# fm_1.net
KiCad netlist of a schematic drawn in EAGLE
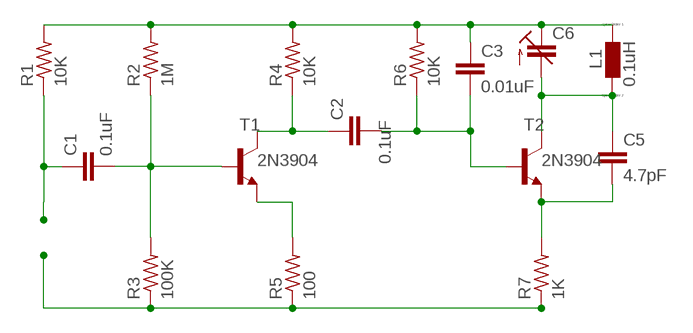
[diagram p0: schematic, sheet 1]

(export (version "E")
  (design (tool "Eeschema 10.0.6"))
  (components
    (comp (ref "C1")
      (value "0.1uF")
      (footprint "eagle-import:C025-040X050")
      (libsource (lib "eagle-import") (part "C-EU025-040X050"))
    )
    (comp (ref "C2")
      (value "0.1uF")
      (footprint "eagle-import:C025-040X050")
      (libsource (lib "eagle-import") (part "C-EU025-040X050"))
    )
    (comp (ref "C3")
      (value "0.01uF")
      (footprint "eagle-import:C025-040X050")
      (libsource (lib "eagle-import") (part "C-EU025-040X050"))
    )
    (comp (ref "C5")
      (value "4.7pF")
      (footprint "eagle-import:C025-040X050")
      (libsource (lib "eagle-import") (part "C-EU025-040X050"))
    )
    (comp (ref "C6")
      (value "C-TRIMM808")
      (footprint "eagle-import:CTRIM808-BC")
      (libsource (lib "eagle-import") (part "C-TRIMM808"))
    )
    (comp (ref "L1")
      (value "0.1uH")
      (footprint "eagle-import:0204_7")
      (libsource (lib "eagle-import") (part "L0204/7"))
    )
    (comp (ref "R1")
      (value "10K")
      (footprint "eagle-import:0204V")
      (libsource (lib "eagle-import") (part "R-US_0204/2V"))
    )
    (comp (ref "R2")
      (value "1M")
      (footprint "eagle-import:0204V")
      (libsource (lib "eagle-import") (part "R-US_0204/2V"))
    )
    (comp (ref "R3")
      (value "100K")
      (footprint "eagle-import:0204V")
      (libsource (lib "eagle-import") (part "R-US_0204/2V"))
    )
    (comp (ref "R4")
      (value "10K")
      (footprint "eagle-import:0204V")
      (libsource (lib "eagle-import") (part "R-US_0204/2V"))
    )
    (comp (ref "R5")
      (value "100")
      (footprint "eagle-import:0204V")
      (libsource (lib "eagle-import") (part "R-US_0204/2V"))
    )
    (comp (ref "R6")
      (value "10K")
      (footprint "eagle-import:0204V")
      (libsource (lib "eagle-import") (part "R-US_0204/2V"))
    )
    (comp (ref "R7")
      (value "1K")
      (footprint "eagle-import:0204V")
      (libsource (lib "eagle-import") (part "R-US_0204/2V"))
    )
    (comp (ref "T1")
      (value "2N3904")
      (footprint "eagle-import:TO92")
      (libsource (lib "eagle-import") (part "2N3904"))
    )
    (comp (ref "T2")
      (value "2N3904")
      (footprint "eagle-import:TO92")
      (libsource (lib "eagle-import") (part "2N3904"))
    )
  )
  (nets
    (net (code "1") (name "Net-(C1-Pad1)") (class "Default")
      (node (ref "C1") (pin "1") (pinfunction "1_1") (pintype "passive"))
      (node (ref "R1") (pin "1") (pinfunction "1_1") (pintype "passive"))
    )
    (net (code "2") (name "Net-(C6-A)") (class "Default")
      (node (ref "C5") (pin "1") (pinfunction "1_1") (pintype "passive"))
      (node (ref "C6") (pin "2") (pinfunction "A_2") (pintype "passive"))
      (node (ref "L1") (pin "2") (pinfunction "2_2") (pintype "passive"))
      (node (ref "T2") (pin "1") (pinfunction "C_1") (pintype "passive"))
    )
    (net (code "3") (name "Net-(C6-E)") (class "Default")
      (node (ref "C3") (pin "1") (pinfunction "1_1") (pintype "passive"))
      (node (ref "C6") (pin "1") (pinfunction "E_1") (pintype "passive"))
      (node (ref "L1") (pin "1") (pinfunction "1_1") (pintype "passive"))
      (node (ref "R1") (pin "2") (pinfunction "2_2") (pintype "passive"))
      (node (ref "R2") (pin "2") (pinfunction "2_2") (pintype "passive"))
      (node (ref "R4") (pin "2") (pinfunction "2_2") (pintype "passive"))
      (node (ref "R6") (pin "2") (pinfunction "2_2") (pintype "passive"))
    )
    (net (code "4") (name "Net-(R3-Pad1)") (class "Default")
      (node (ref "R3") (pin "1") (pinfunction "1_1") (pintype "passive"))
      (node (ref "R5") (pin "1") (pinfunction "1_1") (pintype "passive"))
      (node (ref "R7") (pin "1") (pinfunction "1_1") (pintype "passive"))
    )
    (net (code "5") (name "Net-(T1-B)") (class "Default")
      (node (ref "C1") (pin "2") (pinfunction "2_2") (pintype "passive"))
      (node (ref "R2") (pin "1") (pinfunction "1_1") (pintype "passive"))
      (node (ref "R3") (pin "2") (pinfunction "2_2") (pintype "passive"))
      (node (ref "T1") (pin "2") (pinfunction "B_2") (pintype "passive"))
    )
    (net (code "6") (name "Net-(T1-C)") (class "Default")
      (node (ref "C2") (pin "1") (pinfunction "1_1") (pintype "passive"))
      (node (ref "R4") (pin "1") (pinfunction "1_1") (pintype "passive"))
      (node (ref "T1") (pin "1") (pinfunction "C_1") (pintype "passive"))
    )
    (net (code "7") (name "Net-(T1-E)") (class "Default")
      (node (ref "R5") (pin "2") (pinfunction "2_2") (pintype "passive"))
      (node (ref "T1") (pin "3") (pinfunction "E_3") (pintype "passive"))
    )
    (net (code "8") (name "Net-(T2-B)") (class "Default")
      (node (ref "C2") (pin "2") (pinfunction "2_2") (pintype "passive"))
      (node (ref "C3") (pin "2") (pinfunction "2_2") (pintype "passive"))
      (node (ref "R6") (pin "1") (pinfunction "1_1") (pintype "passive"))
      (node (ref "T2") (pin "2") (pinfunction "B_2") (pintype "passive"))
    )
    (net (code "9") (name "Net-(T2-E)") (class "Default")
      (node (ref "C5") (pin "2") (pinfunction "2_2") (pintype "passive"))
      (node (ref "R7") (pin "2") (pinfunction "2_2") (pintype "passive"))
      (node (ref "T2") (pin "3") (pinfunction "E_3") (pintype "passive"))
    )
  )
)
